# Detectors.net
KiCad netlist of a schematic drawn in EAGLE
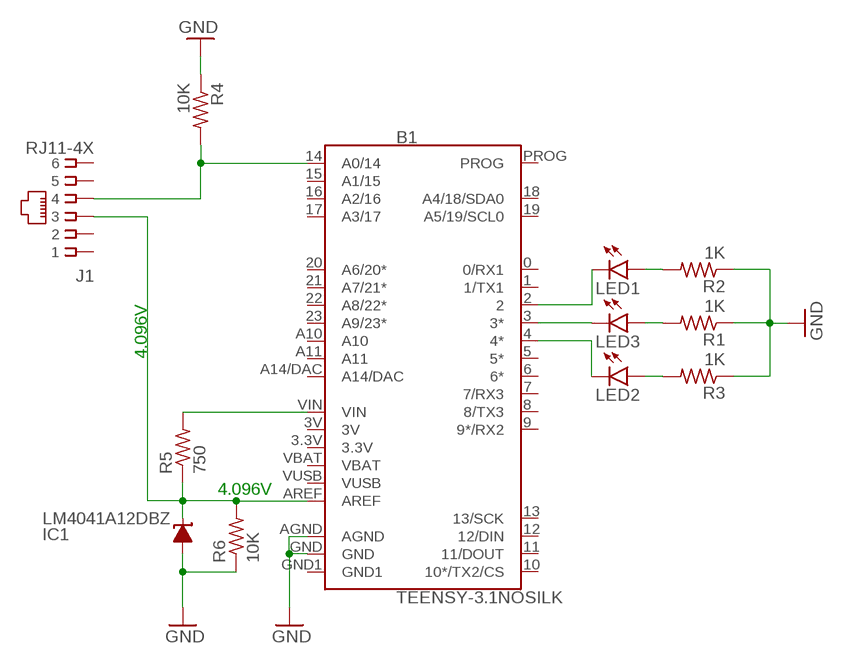
[diagram p0: schematic, sheet 1]

(export (version "E")
  (design (tool "Eeschema 10.0.6"))
  (components
    (comp (ref "B1")
      (value "TEENSY-3.1NOSILK")
      (footprint "eagle-import:TEENSY-3.1_NOSILK")
      (libsource (lib "eagle-import") (part "TEENSY-3.1NOSILK"))
    )
    (comp (ref "IC1")
      (value "LM4041A12DBZ")
      (footprint "eagle-import:DBZ_R-PDSO-G3")
      (fields (field (name "MPN") "LM4041A12IDBZR"))
      (libsource (lib "eagle-import") (part "LM4041DBZA12"))
    )
    (comp (ref "J1")
      (value "RJ11-4X")
      (footprint "eagle-import:RJ11-NO_SHIELD")
      (fields (field (name "MPN") "6609214-3"))
      (libsource (lib "eagle-import") (part "RJ11-4X"))
    )
    (comp (ref "LED1")
      (value "LED5MM")
      (footprint "eagle-import:LED5MM")
      (libsource (lib "eagle-import") (part "LED5MM"))
    )
    (comp (ref "LED2")
      (value "LED5MM")
      (footprint "eagle-import:LED5MM")
      (libsource (lib "eagle-import") (part "LED5MM"))
    )
    (comp (ref "LED3")
      (value "LED5MM")
      (footprint "eagle-import:LED5MM")
      (libsource (lib "eagle-import") (part "LED5MM"))
    )
    (comp (ref "R1")
      (value "1K")
      (footprint "eagle-import:R0805")
      (libsource (lib "eagle-import") (part "R-US_R0805"))
    )
    (comp (ref "R2")
      (value "1K")
      (footprint "eagle-import:R0805")
      (libsource (lib "eagle-import") (part "R-US_R0805"))
    )
    (comp (ref "R3")
      (value "1K")
      (footprint "eagle-import:R0805")
      (libsource (lib "eagle-import") (part "R-US_R0805"))
    )
    (comp (ref "R4")
      (value "10K")
      (footprint "eagle-import:R0805")
      (libsource (lib "eagle-import") (part "R-US_R0805"))
    )
    (comp (ref "R5")
      (value "750")
      (footprint "eagle-import:R0805")
      (libsource (lib "eagle-import") (part "R-US_R0805"))
    )
    (comp (ref "R6")
      (value "10K")
      (footprint "eagle-import:R0805")
      (libsource (lib "eagle-import") (part "R-US_R0805"))
    )
  )
  (nets
    (net (code "1") (name "/3.3V") (class "Default")
      (node (ref "B1") (pin "3.3V") (pinfunction "3.3V_3.3V") (pintype "power_in"))
    )
    (net (code "2") (name "/3V") (class "Default")
      (node (ref "B1") (pin "3V") (pinfunction "3V_3V") (pintype "power_in"))
    )
    (net (code "3") (name "/GND1") (class "Default")
      (node (ref "B1") (pin "GND1") (pinfunction "GND1_GND1") (pintype "power_in"))
    )
    (net (code "4") (name "/VBAT") (class "Default")
      (node (ref "B1") (pin "VBAT") (pinfunction "VBAT_VBAT") (pintype "power_in"))
    )
    (net (code "5") (name "/VUSB") (class "Default")
      (node (ref "B1") (pin "VUSB") (pinfunction "VUSB_VUSB") (pintype "power_in"))
    )
    (net (code "6") (name "GND") (class "Default")
      (node (ref "B1") (pin "AGND") (pinfunction "AGND_AGND") (pintype "power_in"))
      (node (ref "B1") (pin "GND") (pinfunction "GND_GND") (pintype "power_in"))
      (node (ref "IC1") (pin "2") (pinfunction "A_2") (pintype "passive"))
      (node (ref "R1") (pin "1") (pinfunction "1_1") (pintype "passive"))
      (node (ref "R2") (pin "1") (pinfunction "1_1") (pintype "passive"))
      (node (ref "R3") (pin "1") (pinfunction "1_1") (pintype "passive"))
      (node (ref "R4") (pin "1") (pinfunction "1_1") (pintype "passive"))
      (node (ref "R6") (pin "1") (pinfunction "1_1") (pintype "passive"))
    )
    (net (code "7") (name "Net-(B1-3*)") (class "Default")
      (node (ref "B1") (pin "3") (pinfunction "3*_3") (pintype "bidirectional"))
      (node (ref "LED3") (pin "K") (pinfunction "C_K") (pintype "passive"))
    )
    (net (code "8") (name "Net-(B1-4*)") (class "Default")
      (node (ref "B1") (pin "4") (pinfunction "4*_4") (pintype "bidirectional"))
      (node (ref "LED2") (pin "K") (pinfunction "C_K") (pintype "passive"))
    )
    (net (code "9") (name "Net-(B1-A0{slash}14)") (class "Default")
      (node (ref "B1") (pin "14") (pinfunction "A0/14_14") (pintype "bidirectional"))
      (node (ref "J1") (pin "4") (pinfunction "4_4") (pintype "passive"))
      (node (ref "R4") (pin "2") (pinfunction "2_2") (pintype "passive"))
    )
    (net (code "10") (name "Net-(B1-PadVIN)") (class "Default")
      (node (ref "B1") (pin "VIN") (pinfunction "VIN_VIN") (pintype "power_in"))
      (node (ref "R5") (pin "2") (pinfunction "2_2") (pintype "passive"))
    )
    (net (code "11") (name "Net-(IC1-C)") (class "Default")
      (node (ref "B1") (pin "AREF") (pinfunction "AREF_AREF") (pintype "bidirectional"))
      (node (ref "IC1") (pin "1") (pinfunction "C_1") (pintype "passive"))
      (node (ref "J1") (pin "3") (pinfunction "3_3") (pintype "passive"))
      (node (ref "R5") (pin "1") (pinfunction "1_1") (pintype "passive"))
      (node (ref "R6") (pin "2") (pinfunction "2_2") (pintype "passive"))
    )
    (net (code "12") (name "Net-(LED1-C)") (class "Default")
      (node (ref "B1") (pin "2") (pinfunction "2_2") (pintype "bidirectional"))
      (node (ref "LED1") (pin "K") (pinfunction "C_K") (pintype "passive"))
    )
    (net (code "13") (name "Net-(LED1-PadA)") (class "Default")
      (node (ref "LED1") (pin "A") (pinfunction "A_A") (pintype "passive"))
      (node (ref "R2") (pin "2") (pinfunction "2_2") (pintype "passive"))
    )
    (net (code "14") (name "Net-(LED2-PadA)") (class "Default")
      (node (ref "LED2") (pin "A") (pinfunction "A_A") (pintype "passive"))
      (node (ref "R3") (pin "2") (pinfunction "2_2") (pintype "passive"))
    )
    (net (code "15") (name "Net-(LED3-PadA)") (class "Default")
      (node (ref "LED3") (pin "A") (pinfunction "A_A") (pintype "passive"))
      (node (ref "R1") (pin "2") (pinfunction "2_2") (pintype "passive"))
    )
    (net (code "16") (name "unconnected-(B1-0{slash}RX1-Pad0)") (class "Default")
      (node (ref "B1") (pin "0") (pinfunction "0/RX1_0") (pintype "bidirectional"))
    )
    (net (code "17") (name "unconnected-(B1-1{slash}TX1-Pad1)") (class "Default")
      (node (ref "B1") (pin "1") (pinfunction "1/TX1_1") (pintype "bidirectional"))
    )
    (net (code "18") (name "unconnected-(B1-5*-Pad5)") (class "Default")
      (node (ref "B1") (pin "5") (pinfunction "5*_5") (pintype "bidirectional"))
    )
    (net (code "19") (name "unconnected-(B1-6*-Pad6)") (class "Default")
      (node (ref "B1") (pin "6") (pinfunction "6*_6") (pintype "bidirectional"))
    )
    (net (code "20") (name "unconnected-(B1-7{slash}RX3-Pad7)") (class "Default")
      (node (ref "B1") (pin "7") (pinfunction "7/RX3_7") (pintype "bidirectional"))
    )
    (net (code "21") (name "unconnected-(B1-8{slash}TX3-Pad8)") (class "Default")
      (node (ref "B1") (pin "8") (pinfunction "8/TX3_8") (pintype "bidirectional"))
    )
    (net (code "22") (name "unconnected-(B1-9*{slash}RX2-Pad9)") (class "Default")
      (node (ref "B1") (pin "9") (pinfunction "9*/RX2_9") (pintype "bidirectional"))
    )
    (net (code "23") (name "unconnected-(B1-10*{slash}TX2{slash}CS-Pad10)") (class "Default")
      (node (ref "B1") (pin "10") (pinfunction "10*/TX2/CS_10") (pintype "bidirectional"))
    )
    (net (code "24") (name "unconnected-(B1-11{slash}DOUT-Pad11)") (class "Default")
      (node (ref "B1") (pin "11") (pinfunction "11/DOUT_11") (pintype "bidirectional"))
    )
    (net (code "25") (name "unconnected-(B1-12{slash}DIN-Pad12)") (class "Default")
      (node (ref "B1") (pin "12") (pinfunction "12/DIN_12") (pintype "bidirectional"))
    )
    (net (code "26") (name "unconnected-(B1-13{slash}SCK-Pad13)") (class "Default")
      (node (ref "B1") (pin "13") (pinfunction "13/SCK_13") (pintype "bidirectional"))
    )
    (net (code "27") (name "unconnected-(B1-A1{slash}15-Pad15)") (class "Default")
      (node (ref "B1") (pin "15") (pinfunction "A1/15_15") (pintype "bidirectional"))
    )
    (net (code "28") (name "unconnected-(B1-A2{slash}16-Pad16)") (class "Default")
      (node (ref "B1") (pin "16") (pinfunction "A2/16_16") (pintype "bidirectional"))
    )
    (net (code "29") (name "unconnected-(B1-A3{slash}17-Pad17)") (class "Default")
      (node (ref "B1") (pin "17") (pinfunction "A3/17_17") (pintype "bidirectional"))
    )
    (net (code "30") (name "unconnected-(B1-A4{slash}18{slash}SDA0-Pad18)") (class "Default")
      (node (ref "B1") (pin "18") (pinfunction "A4/18/SDA0_18") (pintype "bidirectional"))
    )
    (net (code "31") (name "unconnected-(B1-A5{slash}19{slash}SCL0-Pad19)") (class "Default")
      (node (ref "B1") (pin "19") (pinfunction "A5/19/SCL0_19") (pintype "bidirectional"))
    )
    (net (code "32") (name "unconnected-(B1-A6{slash}20*-Pad20)") (class "Default")
      (node (ref "B1") (pin "20") (pinfunction "A6/20*_20") (pintype "bidirectional"))
    )
    (net (code "33") (name "unconnected-(B1-A7{slash}21*-Pad21)") (class "Default")
      (node (ref "B1") (pin "21") (pinfunction "A7/21*_21") (pintype "bidirectional"))
    )
    (net (code "34") (name "unconnected-(B1-A8{slash}22*-Pad22)") (class "Default")
      (node (ref "B1") (pin "22") (pinfunction "A8/22*_22") (pintype "bidirectional"))
    )
    (net (code "35") (name "unconnected-(B1-A9{slash}23*-Pad23)") (class "Default")
      (node (ref "B1") (pin "23") (pinfunction "A9/23*_23") (pintype "bidirectional"))
    )
    (net (code "36") (name "unconnected-(B1-PadA10)") (class "Default")
      (node (ref "B1") (pin "A10") (pinfunction "A10_A10") (pintype "bidirectional"))
    )
    (net (code "37") (name "unconnected-(B1-PadA11)") (class "Default")
      (node (ref "B1") (pin "A11") (pinfunction "A11_A11") (pintype "bidirectional"))
    )
    (net (code "38") (name "unconnected-(B1-PadA14{slash}DAC)") (class "Default")
      (node (ref "B1") (pin "A14/DAC") (pinfunction "A14/DAC_A14/DAC") (pintype "bidirectional"))
    )
    (net (code "39") (name "unconnected-(B1-PadPROG)") (class "Default")
      (node (ref "B1") (pin "PROG") (pinfunction "PROG_PROG") (pintype "bidirectional"))
    )
    (net (code "40") (name "unconnected-(J1-Pad1)") (class "Default")
      (node (ref "J1") (pin "1") (pinfunction "1_1") (pintype "passive"))
    )
    (net (code "41") (name "unconnected-(J1-Pad2)") (class "Default")
      (node (ref "J1") (pin "2") (pinfunction "2_2") (pintype "passive"))
    )
    (net (code "42") (name "unconnected-(J1-Pad5)") (class "Default")
      (node (ref "J1") (pin "5") (pinfunction "5_5") (pintype "passive"))
    )
    (net (code "43") (name "unconnected-(J1-Pad6)") (class "Default")
      (node (ref "J1") (pin "6") (pinfunction "6_6") (pintype "passive"))
    )
  )
)
